# USB_TO_TTL.net
KiCad netlist of a schematic drawn in Altium Designer
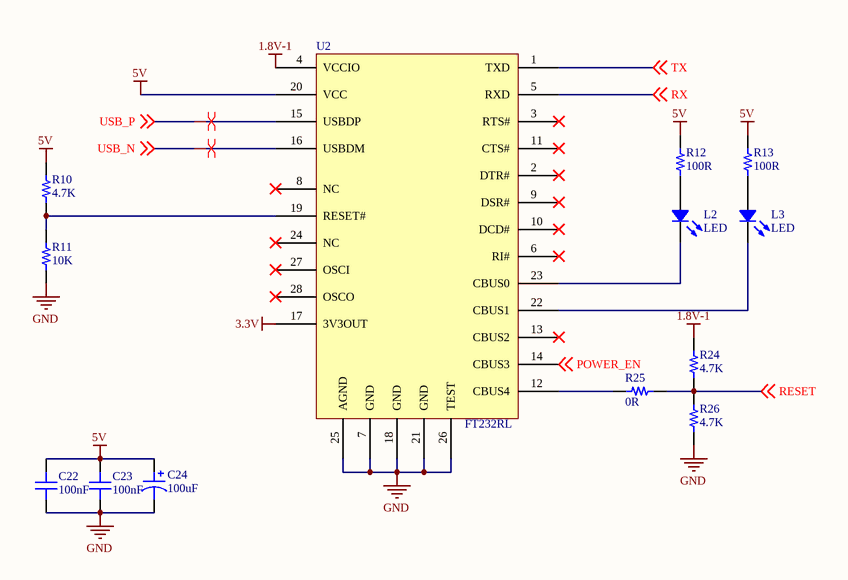
[diagram p0: USB_TO_TTL.SchDoc]

(export (version "E")
  (design (tool "Eeschema 10.0.6"))
  (components
    (comp (ref "C22") (value "100nF") (footprint "CAP-SMD-0402") (libsource (lib "USB_MINER") (part "CAP")))
    (comp (ref "C23") (value "100nF") (footprint "CAP-SMD-0402") (libsource (lib "USB_MINER") (part "CAP")))
    (comp (ref "C24")
      (value "100uF")
      (footprint "CAP-TAN-CASE-B")
      (libsource (lib "USB_MINER") (part "POLARIZED CAP"))
    )
    (comp (ref "L2") (value "LED") (footprint "LED-SMD-0805") (libsource (lib "USB_MINER") (part "LED")))
    (comp (ref "L3") (value "LED") (footprint "LED-SMD-0805") (libsource (lib "USB_MINER") (part "LED")))
    (comp (ref "R10") (value "4.7K") (footprint "RES-SMD-0402") (libsource (lib "USB_MINER") (part "RES")))
    (comp (ref "R11") (value "10K") (footprint "RES-SMD-0402") (libsource (lib "USB_MINER") (part "RES")))
    (comp (ref "R12") (value "100R") (footprint "RES-SMD-0402") (libsource (lib "USB_MINER") (part "RES")))
    (comp (ref "R13") (value "100R") (footprint "RES-SMD-0402") (libsource (lib "USB_MINER") (part "RES")))
    (comp (ref "R24") (value "4.7K") (footprint "RES-SMD-0402") (libsource (lib "USB_MINER") (part "RES")))
    (comp (ref "R25") (value "0R") (footprint "RES-SMD-0402") (libsource (lib "USB_MINER") (part "RES")))
    (comp (ref "R26") (value "4.7K") (footprint "RES-SMD-0402") (libsource (lib "USB_MINER") (part "RES")))
    (comp (ref "U2") (value "FT232RL") (footprint "SSOP") (libsource (lib "USB_MINER") (part "FT232RL")))
  )
  (nets
    (net (code "1") (name "1.8V-1") (class "Default")
      (node (ref "R24") (pin "2") (pinfunction "2_2") (pintype "passive"))
      (node (ref "U2") (pin "4") (pinfunction "VCCIO_4") (pintype "passive"))
    )
    (net (code "2") (name "3.3V") (class "Default")
      (node (ref "U2") (pin "17") (pinfunction "3V3OUT_17") (pintype "passive"))
    )
    (net (code "3") (name "5V") (class "Default")
      (node (ref "C22") (pin "2") (pinfunction "2_2") (pintype "passive"))
      (node (ref "C23") (pin "2") (pinfunction "2_2") (pintype "passive"))
      (node (ref "C24") (pin "1") (pinfunction "1_1") (pintype "passive"))
      (node (ref "R10") (pin "2") (pinfunction "2_2") (pintype "passive"))
      (node (ref "R12") (pin "2") (pinfunction "2_2") (pintype "passive"))
      (node (ref "R13") (pin "2") (pinfunction "2_2") (pintype "passive"))
      (node (ref "U2") (pin "20") (pinfunction "VCC_20") (pintype "passive"))
    )
    (net (code "4") (name "GND") (class "Default")
      (node (ref "C22") (pin "1") (pinfunction "1_1") (pintype "passive"))
      (node (ref "C23") (pin "1") (pinfunction "1_1") (pintype "passive"))
      (node (ref "C24") (pin "2") (pinfunction "2_2") (pintype "passive"))
      (node (ref "R11") (pin "1") (pinfunction "1_1") (pintype "passive"))
      (node (ref "R26") (pin "1") (pinfunction "1_1") (pintype "passive"))
      (node (ref "U2") (pin "18") (pinfunction "GND_18") (pintype "passive"))
      (node (ref "U2") (pin "21") (pinfunction "GND_21") (pintype "passive"))
      (node (ref "U2") (pin "25") (pinfunction "AGND_25") (pintype "passive"))
      (node (ref "U2") (pin "26") (pinfunction "TEST_26") (pintype "passive"))
      (node (ref "U2") (pin "7") (pinfunction "GND_7") (pintype "passive"))
    )
    (net (code "5") (name "Net-(L2-Pad1)") (class "Default")
      (node (ref "L2") (pin "1") (pinfunction "1_1") (pintype "passive"))
      (node (ref "R12") (pin "1") (pinfunction "1_1") (pintype "passive"))
    )
    (net (code "6") (name "Net-(L3-Pad1)") (class "Default")
      (node (ref "L3") (pin "1") (pinfunction "1_1") (pintype "passive"))
      (node (ref "R13") (pin "1") (pinfunction "1_1") (pintype "passive"))
    )
    (net (code "7") (name "Net-(U2-CBUS0)") (class "Default")
      (node (ref "L2") (pin "2") (pinfunction "2_2") (pintype "passive"))
      (node (ref "U2") (pin "23") (pinfunction "CBUS0_23") (pintype "passive"))
    )
    (net (code "8") (name "Net-(U2-CBUS1)") (class "Default")
      (node (ref "L3") (pin "2") (pinfunction "2_2") (pintype "passive"))
      (node (ref "U2") (pin "22") (pinfunction "CBUS1_22") (pintype "passive"))
    )
    (net (code "9") (name "Net-(U2-CBUS4)") (class "Default")
      (node (ref "R25") (pin "2") (pinfunction "2_2") (pintype "passive"))
      (node (ref "U2") (pin "12") (pinfunction "CBUS4_12") (pintype "passive"))
    )
    (net (code "10") (name "Net-(U2-RESET#)") (class "Default")
      (node (ref "R10") (pin "1") (pinfunction "1_1") (pintype "passive"))
      (node (ref "R11") (pin "2") (pinfunction "2_2") (pintype "passive"))
      (node (ref "U2") (pin "19") (pinfunction "RESET#_19") (pintype "passive"))
    )
    (net (code "11") (name "POWER_EN") (class "Default")
      (node (ref "U2") (pin "14") (pinfunction "CBUS3_14") (pintype "passive"))
    )
    (net (code "12") (name "RESET") (class "Default")
      (node (ref "R24") (pin "1") (pinfunction "1_1") (pintype "passive"))
      (node (ref "R25") (pin "1") (pinfunction "1_1") (pintype "passive"))
      (node (ref "R26") (pin "2") (pinfunction "2_2") (pintype "passive"))
    )
    (net (code "13") (name "RX") (class "Default")
      (node (ref "U2") (pin "5") (pinfunction "RXD_5") (pintype "passive"))
    )
    (net (code "14") (name "TX") (class "Default")
      (node (ref "U2") (pin "1") (pinfunction "TXD_1") (pintype "passive"))
    )
    (net (code "15") (name "USB_N") (class "Default")
      (node (ref "U2") (pin "16") (pinfunction "USBDM_16") (pintype "passive"))
    )
    (net (code "16") (name "USB_P") (class "Default")
      (node (ref "U2") (pin "15") (pinfunction "USBDP_15") (pintype "passive"))
    )
    (net (code "17") (name "unconnected-(U2-CBUS2-Pad13)") (class "Default")
      (node (ref "U2") (pin "13") (pinfunction "CBUS2_13") (pintype "passive+no_connect"))
    )
    (net (code "18") (name "unconnected-(U2-CTS#-Pad11)") (class "Default")
      (node (ref "U2") (pin "11") (pinfunction "CTS#_11") (pintype "passive+no_connect"))
    )
    (net (code "19") (name "unconnected-(U2-DCD#-Pad10)") (class "Default")
      (node (ref "U2") (pin "10") (pinfunction "DCD#_10") (pintype "passive+no_connect"))
    )
    (net (code "20") (name "unconnected-(U2-DSR#-Pad9)") (class "Default")
      (node (ref "U2") (pin "9") (pinfunction "DSR#_9") (pintype "passive+no_connect"))
    )
    (net (code "21") (name "unconnected-(U2-DTR#-Pad2)") (class "Default")
      (node (ref "U2") (pin "2") (pinfunction "DTR#_2") (pintype "passive+no_connect"))
    )
    (net (code "22") (name "unconnected-(U2-NC-Pad8)") (class "Default")
      (node (ref "U2") (pin "8") (pinfunction "NC_8") (pintype "passive+no_connect"))
    )
    (net (code "23") (name "unconnected-(U2-NC-Pad24)") (class "Default")
      (node (ref "U2") (pin "24") (pinfunction "NC_24") (pintype "passive+no_connect"))
    )
    (net (code "24") (name "unconnected-(U2-OSCI-Pad27)") (class "Default")
      (node (ref "U2") (pin "27") (pinfunction "OSCI_27") (pintype "passive+no_connect"))
    )
    (net (code "25") (name "unconnected-(U2-OSCO-Pad28)") (class "Default")
      (node (ref "U2") (pin "28") (pinfunction "OSCO_28") (pintype "passive+no_connect"))
    )
    (net (code "26") (name "unconnected-(U2-RI#-Pad6)") (class "Default")
      (node (ref "U2") (pin "6") (pinfunction "RI#_6") (pintype "passive+no_connect"))
    )
    (net (code "27") (name "unconnected-(U2-RTS#-Pad3)") (class "Default")
      (node (ref "U2") (pin "3") (pinfunction "RTS#_3") (pintype "passive+no_connect"))
    )
  )
)
